# ProProject___2024-06-28.net
KiCad netlist of a schematic drawn in EasyEDA Pro
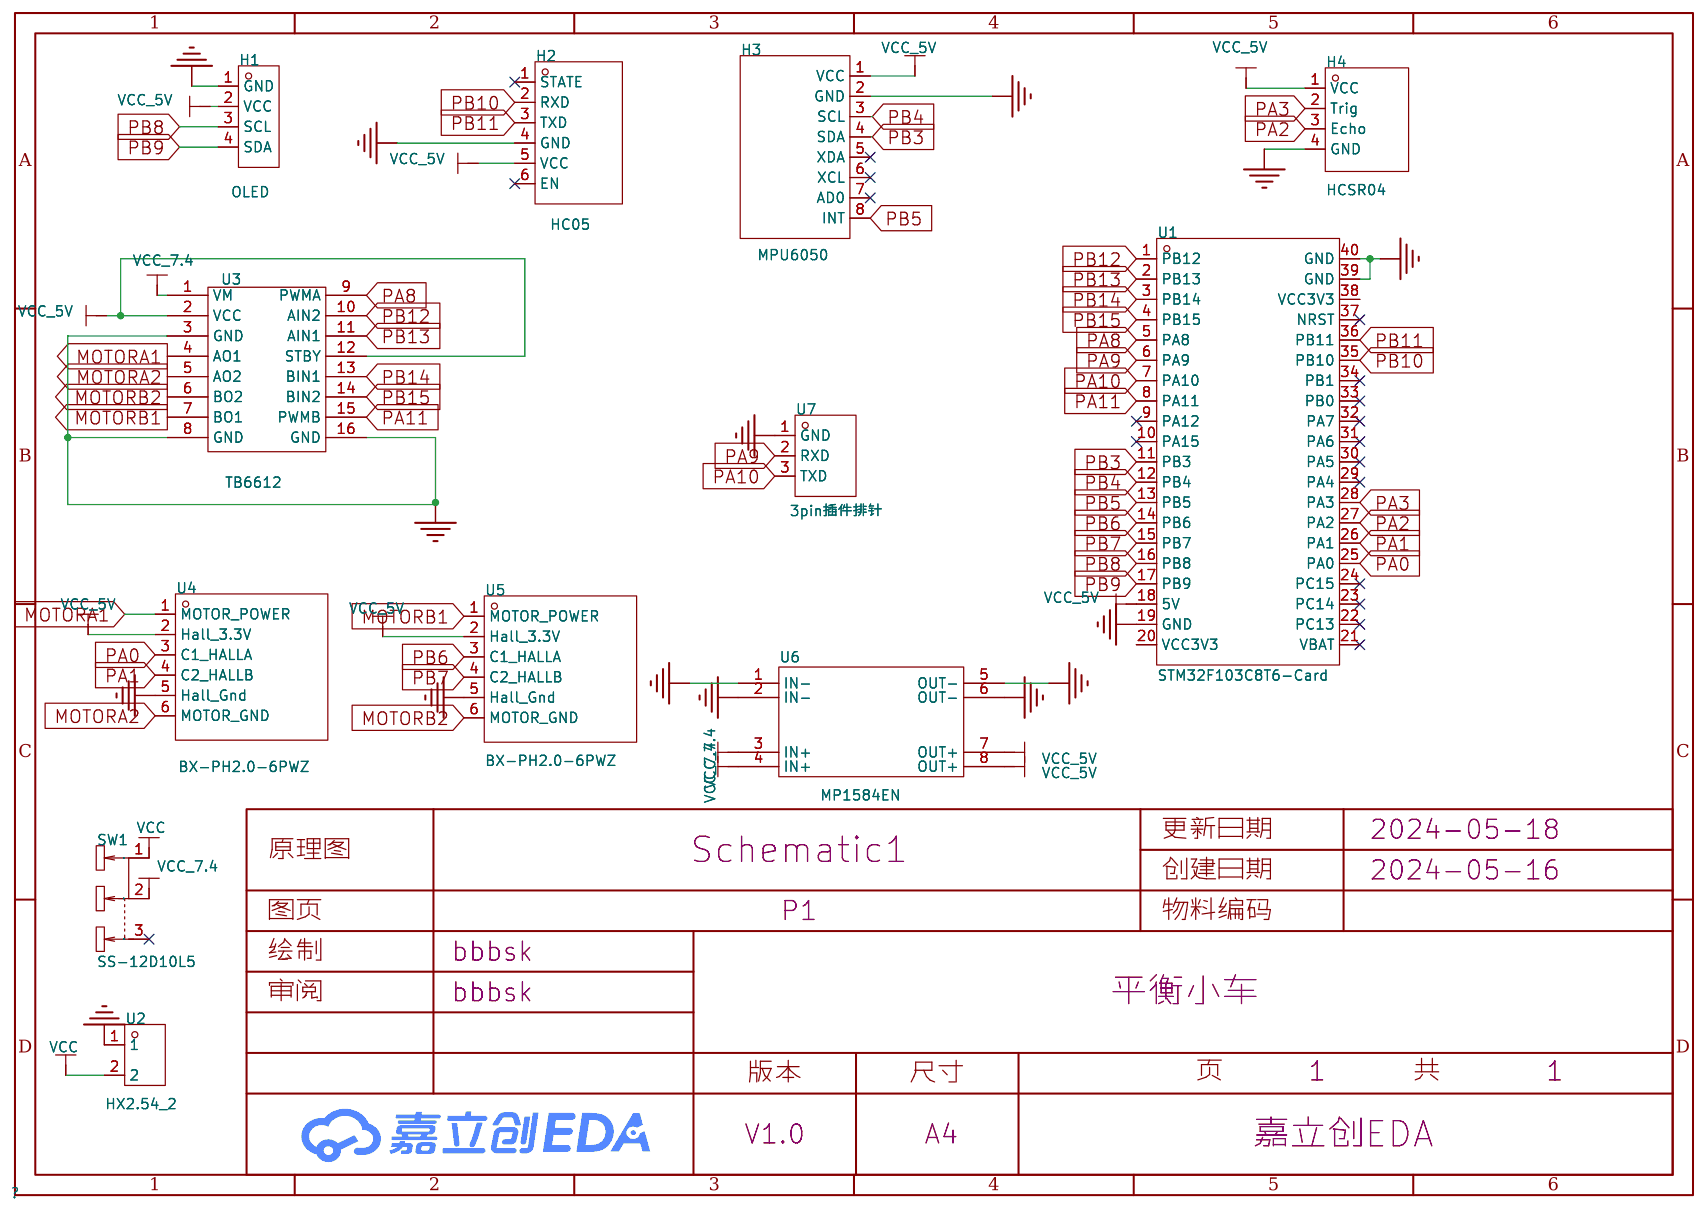
[diagram p0: schematic sheet]

(export (version "E")
  (design (tool "Eeschema 10.0.6"))
  (components
    (comp (ref "H1")
      (value "OLED")
      (footprint "easyedapro:HDR-TH_4P-P2.54-V-F")
      (fields (field (name "Manufacturer Part") "2.54-1*4P母") (field (name "Manufacturer") "BOOMELE(博穆精密)"))
      (libsource (lib "easyedapro") (part "OLED排母"))
    )
    (comp (ref "H2")
      (value "HC05")
      (footprint "easyedapro:HDR-TH_6P-P2.54-V-F")
      (description "插孔结构:1x6P;间距:2.54mm;行距:-;安装类型:直插;排数:单排;总孔位数:6P;塑高:-;触头材质:-;触头镀层:-;")
      (fields (field (name "Manufacturer Part") "2.54-1*6P母") (field (name "Manufacturer") "BOOMELE(博穆精密)"))
      (libsource (lib "easyedapro") (part "HC05"))
    )
    (comp (ref "H3")
      (value "MPU6050")
      (footprint "easyedapro:HDR-TH_8P-P2.54-V-F-1")
      (description "插孔结构:1x8P;间距:2.54mm;行距:-;安装类型:直插;排数:单排;总孔位数:8P;塑高:-;触头材质:-;触头镀层:-;")
      (fields (field (name "Manufacturer Part") "2.54-1*8P母环保") (field (name "Manufacturer") "BOOMELE(博穆精密)"))
      (libsource (lib "easyedapro") (part "MPU6050"))
    )
    (comp (ref "H4")
      (value "HCSR04")
      (footprint "easyedapro:HDR-TH_4P-P2.54-V-F")
      (fields (field (name "Manufacturer Part") "2.54-1*4P母") (field (name "Manufacturer") "BOOMELE(博穆精密)"))
      (libsource (lib "easyedapro") (part "HCSR04"))
    )
    (comp (ref "SW1")
      (value "SS-12D10L5")
      (footprint "easyedapro:SW-TH_SS-12D10L5")
      (description "电路结构:单刀双掷;安装方式:直插;开关颜色:黑色;额定电流(DC):3A;额定电压(DC):125V;额定电流(AC):3A;额定电压(AC):125V;机械寿命:1万次;")
      (fields (field (name "Manufacturer") "XKB Connectivity(中国星坤)"))
      (libsource (lib "easyedapro") (part "SS-12D10L5"))
    )
    (comp (ref "U1")
      (value "STM32F103C8T6-Card")
      (footprint "easyedapro:CONN-TH_L53.3-W22.9_STM32F103C8T6-CARD")
      (libsource (lib "easyedapro") (part "STM32F103C8T6-CARD"))
    )
    (comp (ref "U2")
      (value "HX2.54_2")
      (footprint "easyedapro:CONN-TH_2P-P2.50_HX254")
      (libsource (lib "easyedapro") (part "HX2.54_2"))
    )
    (comp (ref "U3") (value "TB6612") (libsource (lib "easyedapro") (part "TB6612")))
    (comp (ref "U4")
      (value "BX-PH2.0-6PWZ")
      (footprint "easyedapro:CONN-TH_6P-P2.00_BX-PH2.0-6PWZ")
      (fields (field (name "Manufacturer") "Bossie(博锡)"))
      (libsource (lib "easyedapro") (part "BX-PH2.0-6PWZ"))
    )
    (comp (ref "U5")
      (value "BX-PH2.0-6PWZ")
      (footprint "easyedapro:CONN-TH_6P-P2.00_BX-PH2.0-6PWZ")
      (fields (field (name "Manufacturer") "Bossie(博锡)"))
      (libsource (lib "easyedapro") (part "BX-PH2.0-6PWZ"))
    )
    (comp (ref "U6") (value "MP1584EN") (libsource (lib "easyedapro") (part "MP1584EN")))
    (comp (ref "U7")
      (value "3pin插件排针")
      (footprint "easyedapro:HDR-TH_3P-P2.00-V-M")
      (libsource (lib "easyedapro") (part "串口调试"))
    )
  )
  (nets
    (net (code "1") (name "GND") (class "Default")
      (node (ref "H1") (pin "1") (pinfunction "GND_1") (pintype "unspecified"))
      (node (ref "H2") (pin "4") (pinfunction "GND_4") (pintype "unspecified"))
      (node (ref "H3") (pin "2") (pinfunction "GND_2") (pintype "input"))
      (node (ref "H4") (pin "4") (pinfunction "GND_4") (pintype "unspecified"))
      (node (ref "U1") (pin "19") (pinfunction "GND_19") (pintype "unspecified"))
      (node (ref "U1") (pin "39") (pinfunction "GND_39") (pintype "unspecified"))
      (node (ref "U1") (pin "40") (pinfunction "GND_40") (pintype "unspecified"))
      (node (ref "U2") (pin "1") (pinfunction "1_1") (pintype "unspecified"))
      (node (ref "U3") (pin "16") (pinfunction "GND_16") (pintype "input"))
      (node (ref "U3") (pin "3") (pinfunction "GND_3") (pintype "input"))
      (node (ref "U3") (pin "8") (pinfunction "GND_8") (pintype "input"))
      (node (ref "U4") (pin "5") (pinfunction "Hall_Gnd_5") (pintype "unspecified"))
      (node (ref "U5") (pin "5") (pinfunction "Hall_Gnd_5") (pintype "unspecified"))
      (node (ref "U6") (pin "1") (pinfunction "IN-_1") (pintype "input"))
      (node (ref "U6") (pin "2") (pinfunction "IN-_2") (pintype "input"))
      (node (ref "U6") (pin "5") (pinfunction "OUT-_5") (pintype "input"))
      (node (ref "U6") (pin "6") (pinfunction "OUT-_6") (pintype "input"))
      (node (ref "U7") (pin "1") (pinfunction "GND_1") (pintype "unspecified"))
    )
    (net (code "2") (name "MOTORA1") (class "Default")
      (node (ref "U3") (pin "4") (pinfunction "AO1_4") (pintype "input"))
      (node (ref "U4") (pin "1") (pinfunction "MOTOR_POWER_1") (pintype "unspecified"))
    )
    (net (code "3") (name "MOTORA2") (class "Default")
      (node (ref "U3") (pin "5") (pinfunction "AO2_5") (pintype "input"))
      (node (ref "U4") (pin "6") (pinfunction "MOTOR_GND_6") (pintype "unspecified"))
    )
    (net (code "4") (name "MOTORB1") (class "Default")
      (node (ref "U3") (pin "7") (pinfunction "BO1_7") (pintype "input"))
      (node (ref "U5") (pin "1") (pinfunction "MOTOR_POWER_1") (pintype "unspecified"))
    )
    (net (code "5") (name "MOTORB2") (class "Default")
      (node (ref "U3") (pin "6") (pinfunction "BO2_6") (pintype "input"))
      (node (ref "U5") (pin "6") (pinfunction "MOTOR_GND_6") (pintype "unspecified"))
    )
    (net (code "6") (name "PA0") (class "Default")
      (node (ref "U1") (pin "25") (pinfunction "PA0_25") (pintype "unspecified"))
      (node (ref "U4") (pin "3") (pinfunction "C1_HALLA_3") (pintype "unspecified"))
    )
    (net (code "7") (name "PA1") (class "Default")
      (node (ref "U1") (pin "26") (pinfunction "PA1_26") (pintype "unspecified"))
      (node (ref "U4") (pin "4") (pinfunction "C2_HALLB_4") (pintype "unspecified"))
    )
    (net (code "8") (name "PA2") (class "Default")
      (node (ref "H4") (pin "3") (pinfunction "Echo_3") (pintype "unspecified"))
      (node (ref "U1") (pin "27") (pinfunction "PA2_27") (pintype "unspecified"))
    )
    (net (code "9") (name "PA3") (class "Default")
      (node (ref "H4") (pin "2") (pinfunction "Trig_2") (pintype "unspecified"))
      (node (ref "U1") (pin "28") (pinfunction "PA3_28") (pintype "unspecified"))
    )
    (net (code "10") (name "PA8") (class "Default")
      (node (ref "U1") (pin "5") (pinfunction "PA8_5") (pintype "unspecified"))
      (node (ref "U3") (pin "9") (pinfunction "PWMA_9") (pintype "input"))
    )
    (net (code "11") (name "PA9") (class "Default")
      (node (ref "U1") (pin "6") (pinfunction "PA9_6") (pintype "unspecified"))
      (node (ref "U7") (pin "2") (pinfunction "RXD_2") (pintype "unspecified"))
    )
    (net (code "12") (name "PA10") (class "Default")
      (node (ref "U1") (pin "7") (pinfunction "PA10_7") (pintype "unspecified"))
      (node (ref "U7") (pin "3") (pinfunction "TXD_3") (pintype "unspecified"))
    )
    (net (code "13") (name "PA11") (class "Default")
      (node (ref "U1") (pin "8") (pinfunction "PA11_8") (pintype "unspecified"))
      (node (ref "U3") (pin "15") (pinfunction "PWMB_15") (pintype "input"))
    )
    (net (code "14") (name "PB3") (class "Default")
      (node (ref "H3") (pin "4") (pinfunction "SDA_4") (pintype "bidirectional"))
      (node (ref "U1") (pin "11") (pinfunction "PB3_11") (pintype "unspecified"))
    )
    (net (code "15") (name "PB4") (class "Default")
      (node (ref "H3") (pin "3") (pinfunction "SCL_3") (pintype "input"))
      (node (ref "U1") (pin "12") (pinfunction "PB4_12") (pintype "unspecified"))
    )
    (net (code "16") (name "PB5") (class "Default")
      (node (ref "H3") (pin "8") (pinfunction "INT_8") (pintype "input"))
      (node (ref "U1") (pin "13") (pinfunction "PB5_13") (pintype "unspecified"))
    )
    (net (code "17") (name "PB6") (class "Default")
      (node (ref "U1") (pin "14") (pinfunction "PB6_14") (pintype "unspecified"))
      (node (ref "U5") (pin "3") (pinfunction "C1_HALLA_3") (pintype "unspecified"))
    )
    (net (code "18") (name "PB7") (class "Default")
      (node (ref "U1") (pin "15") (pinfunction "PB7_15") (pintype "unspecified"))
      (node (ref "U5") (pin "4") (pinfunction "C2_HALLB_4") (pintype "unspecified"))
    )
    (net (code "19") (name "PB8") (class "Default")
      (node (ref "H1") (pin "3") (pinfunction "SCL_3") (pintype "unspecified"))
      (node (ref "U1") (pin "16") (pinfunction "PB8_16") (pintype "unspecified"))
    )
    (net (code "20") (name "PB9") (class "Default")
      (node (ref "H1") (pin "4") (pinfunction "SDA_4") (pintype "unspecified"))
      (node (ref "U1") (pin "17") (pinfunction "PB9_17") (pintype "unspecified"))
    )
    (net (code "21") (name "PB10") (class "Default")
      (node (ref "H2") (pin "2") (pinfunction "RXD_2") (pintype "unspecified"))
      (node (ref "U1") (pin "35") (pinfunction "PB10_35") (pintype "unspecified"))
    )
    (net (code "22") (name "PB11") (class "Default")
      (node (ref "H2") (pin "3") (pinfunction "TXD_3") (pintype "unspecified"))
      (node (ref "U1") (pin "36") (pinfunction "PB11_36") (pintype "unspecified"))
    )
    (net (code "23") (name "PB12") (class "Default")
      (node (ref "U1") (pin "1") (pinfunction "PB12_1") (pintype "unspecified"))
      (node (ref "U3") (pin "10") (pinfunction "AIN2_10") (pintype "input"))
    )
    (net (code "24") (name "PB13") (class "Default")
      (node (ref "U1") (pin "2") (pinfunction "PB13_2") (pintype "unspecified"))
      (node (ref "U3") (pin "11") (pinfunction "AIN1_11") (pintype "input"))
    )
    (net (code "25") (name "PB14") (class "Default")
      (node (ref "U1") (pin "3") (pinfunction "PB14_3") (pintype "unspecified"))
      (node (ref "U3") (pin "13") (pinfunction "BIN1_13") (pintype "input"))
    )
    (net (code "26") (name "PB15") (class "Default")
      (node (ref "U1") (pin "4") (pinfunction "PB15_4") (pintype "unspecified"))
      (node (ref "U3") (pin "14") (pinfunction "BIN2_14") (pintype "input"))
    )
    (net (code "27") (name "VCC") (class "Default")
      (node (ref "SW1") (pin "1") (pinfunction "1_1") (pintype "unspecified"))
      (node (ref "U2") (pin "2") (pinfunction "2_2") (pintype "unspecified"))
    )
    (net (code "28") (name "VCC_5V") (class "Default")
      (node (ref "H1") (pin "2") (pinfunction "VCC_2") (pintype "unspecified"))
      (node (ref "H2") (pin "5") (pinfunction "VCC_5") (pintype "unspecified"))
      (node (ref "H3") (pin "1") (pinfunction "VCC_1") (pintype "input"))
      (node (ref "H4") (pin "1") (pinfunction "VCC_1") (pintype "unspecified"))
      (node (ref "U1") (pin "18") (pinfunction "5V_18") (pintype "unspecified"))
      (node (ref "U3") (pin "12") (pinfunction "STBY_12") (pintype "input"))
      (node (ref "U3") (pin "2") (pinfunction "VCC_2") (pintype "input"))
      (node (ref "U4") (pin "2") (pinfunction "Hall_3.3V_2") (pintype "unspecified"))
      (node (ref "U5") (pin "2") (pinfunction "Hall_3.3V_2") (pintype "unspecified"))
      (node (ref "U6") (pin "7") (pinfunction "OUT+_7") (pintype "input"))
      (node (ref "U6") (pin "8") (pinfunction "OUT+_8") (pintype "input"))
    )
    (net (code "29") (name "VCC_7.4") (class "Default")
      (node (ref "SW1") (pin "2") (pinfunction "2_2") (pintype "unspecified"))
      (node (ref "U3") (pin "1") (pinfunction "VM_1") (pintype "input"))
      (node (ref "U6") (pin "3") (pinfunction "IN+_3") (pintype "input"))
      (node (ref "U6") (pin "4") (pinfunction "IN+_4") (pintype "input"))
    )
    (net (code "30") (name "unconnected-(H2-EN-Pad6)") (class "Default")
      (node (ref "H2") (pin "6") (pinfunction "EN_6") (pintype "unspecified+no_connect"))
    )
    (net (code "31") (name "unconnected-(H2-STATE-Pad1)") (class "Default")
      (node (ref "H2") (pin "1") (pinfunction "STATE_1") (pintype "unspecified+no_connect"))
    )
    (net (code "32") (name "unconnected-(H3-AD0-Pad7)") (class "Default")
      (node (ref "H3") (pin "7") (pinfunction "AD0_7") (pintype "input+no_connect"))
    )
    (net (code "33") (name "unconnected-(H3-XCL-Pad6)") (class "Default")
      (node (ref "H3") (pin "6") (pinfunction "XCL_6") (pintype "input+no_connect"))
    )
    (net (code "34") (name "unconnected-(H3-XDA-Pad5)") (class "Default")
      (node (ref "H3") (pin "5") (pinfunction "XDA_5") (pintype "input+no_connect"))
    )
    (net (code "35") (name "unconnected-(SW1-Pad3)") (class "Default")
      (node (ref "SW1") (pin "3") (pinfunction "3_3") (pintype "unspecified+no_connect"))
    )
    (net (code "36") (name "unconnected-(U1-NRST-Pad37)") (class "Default")
      (node (ref "U1") (pin "37") (pinfunction "NRST_37") (pintype "unspecified+no_connect"))
    )
    (net (code "37") (name "unconnected-(U1-PA4-Pad29)") (class "Default")
      (node (ref "U1") (pin "29") (pinfunction "PA4_29") (pintype "unspecified+no_connect"))
    )
    (net (code "38") (name "unconnected-(U1-PA5-Pad30)") (class "Default")
      (node (ref "U1") (pin "30") (pinfunction "PA5_30") (pintype "unspecified+no_connect"))
    )
    (net (code "39") (name "unconnected-(U1-PA6-Pad31)") (class "Default")
      (node (ref "U1") (pin "31") (pinfunction "PA6_31") (pintype "unspecified+no_connect"))
    )
    (net (code "40") (name "unconnected-(U1-PA7-Pad32)") (class "Default")
      (node (ref "U1") (pin "32") (pinfunction "PA7_32") (pintype "unspecified+no_connect"))
    )
    (net (code "41") (name "unconnected-(U1-PA12-Pad9)") (class "Default")
      (node (ref "U1") (pin "9") (pinfunction "PA12_9") (pintype "unspecified+no_connect"))
    )
    (net (code "42") (name "unconnected-(U1-PA15-Pad10)") (class "Default")
      (node (ref "U1") (pin "10") (pinfunction "PA15_10") (pintype "unspecified+no_connect"))
    )
    (net (code "43") (name "unconnected-(U1-PB0-Pad33)") (class "Default")
      (node (ref "U1") (pin "33") (pinfunction "PB0_33") (pintype "unspecified+no_connect"))
    )
    (net (code "44") (name "unconnected-(U1-PB1-Pad34)") (class "Default")
      (node (ref "U1") (pin "34") (pinfunction "PB1_34") (pintype "unspecified+no_connect"))
    )
    (net (code "45") (name "unconnected-(U1-PC13-Pad22)") (class "Default")
      (node (ref "U1") (pin "22") (pinfunction "PC13_22") (pintype "unspecified+no_connect"))
    )
    (net (code "46") (name "unconnected-(U1-PC14-Pad23)") (class "Default")
      (node (ref "U1") (pin "23") (pinfunction "PC14_23") (pintype "unspecified+no_connect"))
    )
    (net (code "47") (name "unconnected-(U1-PC15-Pad24)") (class "Default")
      (node (ref "U1") (pin "24") (pinfunction "PC15_24") (pintype "unspecified+no_connect"))
    )
    (net (code "48") (name "unconnected-(U1-VBAT-Pad21)") (class "Default")
      (node (ref "U1") (pin "21") (pinfunction "VBAT_21") (pintype "unspecified+no_connect"))
    )
    (net (code "49") (name "unconnected-(U1-VCC3V3-Pad20)") (class "Default")
      (node (ref "U1") (pin "20") (pinfunction "VCC3V3_20") (pintype "unspecified"))
    )
    (net (code "50") (name "unconnected-(U1-VCC3V3-Pad38)") (class "Default")
      (node (ref "U1") (pin "38") (pinfunction "VCC3V3_38") (pintype "unspecified"))
    )
  )
)
